# Combo_1.net
KiCad netlist of a schematic drawn in Altium Designer
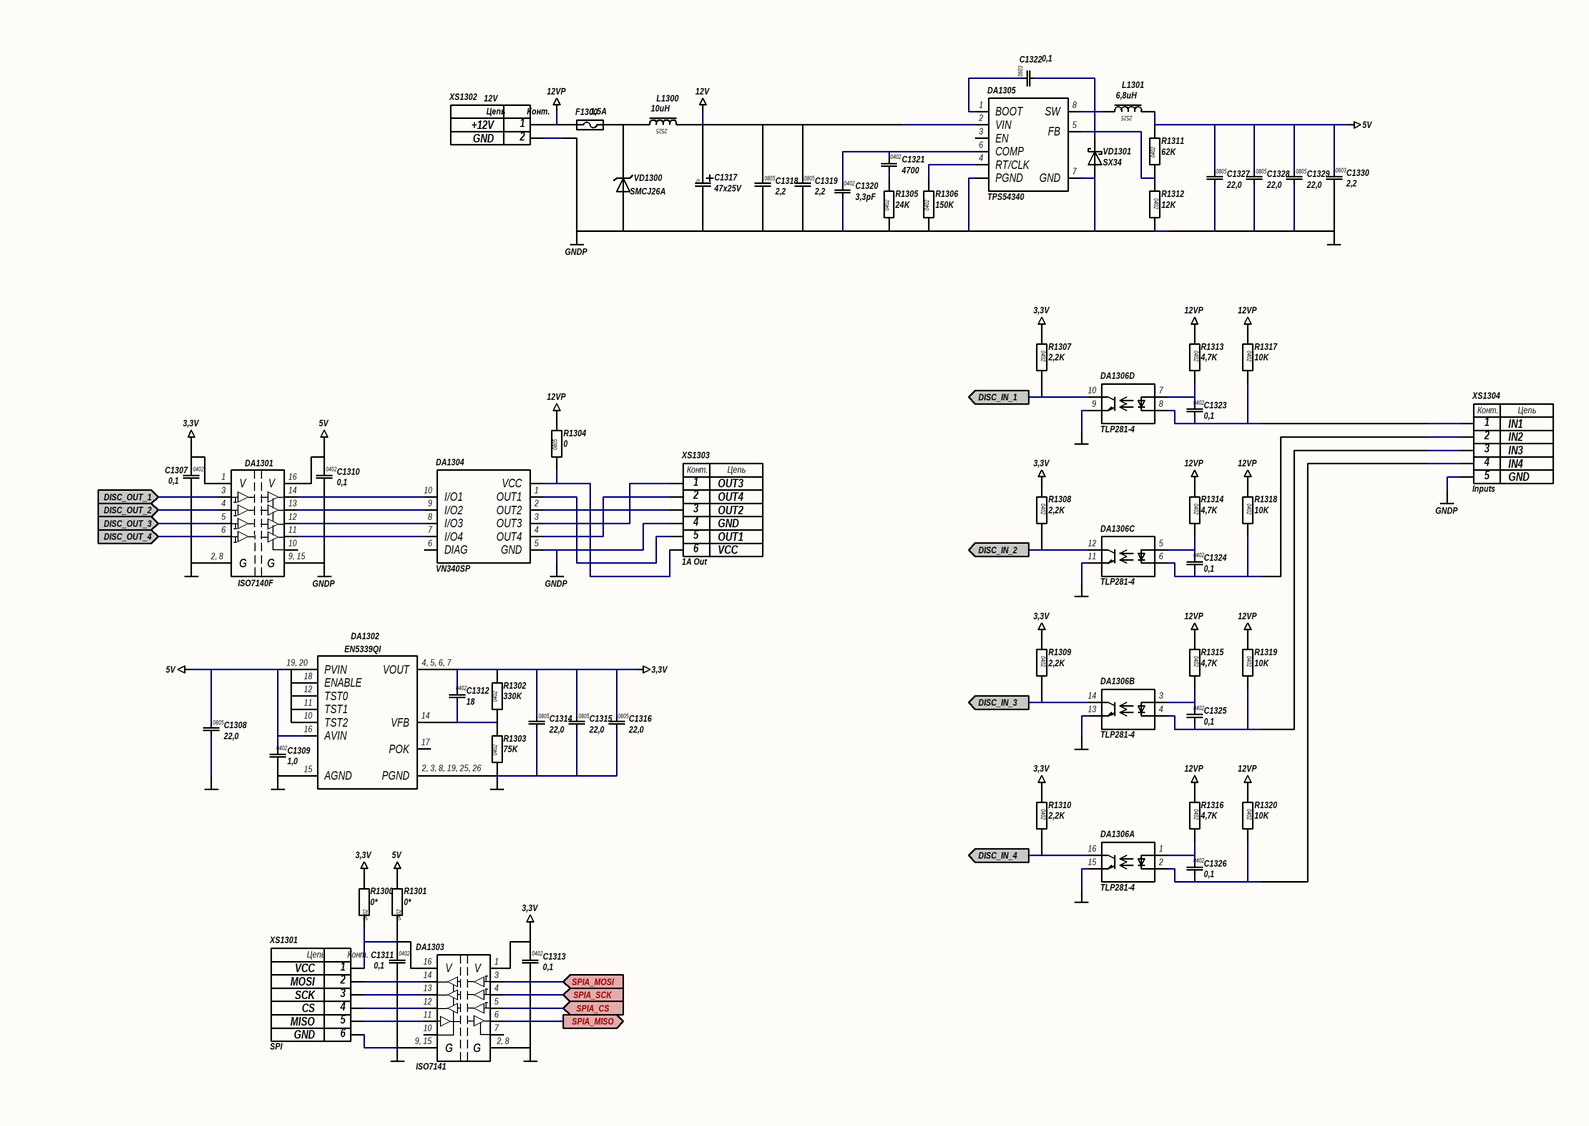
[diagram p0: Combo 1.SchDoc]

(export (version "E")
  (design (tool "Eeschema 10.0.6"))
  (components
    (comp (ref "*1300")
      (value "Перемычка")
      (footprint "Перемычка")
      (libsource (lib "EwgPassive") (part "Перемычка"))
    )
    (comp (ref "C1307")
      (value "0,1")
      (footprint "CAP0402")
      (description "Конденсатор чип")
      (libsource (lib "EwgPassive") (part "CAP_0402"))
    )
    (comp (ref "C1308")
      (value "22,0")
      (footprint "CAP0805")
      (description "Конденсатор чип")
      (libsource (lib "EwgPassive") (part "CAP_0805"))
    )
    (comp (ref "C1309")
      (value "1,0")
      (footprint "CAP0402")
      (description "Конденсатор чип")
      (libsource (lib "EwgPassive") (part "CAP_0402"))
    )
    (comp (ref "C1310")
      (value "0,1")
      (footprint "CAP0402")
      (description "Конденсатор чип")
      (libsource (lib "EwgPassive") (part "CAP_0402"))
    )
    (comp (ref "C1311")
      (value "0,1")
      (footprint "CAP0402")
      (description "Конденсатор чип")
      (libsource (lib "EwgPassive") (part "CAP_0402"))
    )
    (comp (ref "C1312")
      (value "18")
      (footprint "CAP0402")
      (description "Конденсатор чип")
      (libsource (lib "EwgPassive") (part "CAP_0402"))
    )
    (comp (ref "C1313")
      (value "0,1")
      (footprint "CAP0402")
      (description "Конденсатор чип")
      (libsource (lib "EwgPassive") (part "CAP_0402"))
    )
    (comp (ref "C1314")
      (value "22,0")
      (footprint "CAP0805")
      (description "Конденсатор чип")
      (libsource (lib "EwgPassive") (part "CAP_0805"))
    )
    (comp (ref "C1315")
      (value "22,0")
      (footprint "CAP0805")
      (description "Конденсатор чип")
      (libsource (lib "EwgPassive") (part "CAP_0805"))
    )
    (comp (ref "C1316")
      (value "22,0")
      (footprint "CAP0805")
      (description "Конденсатор чип")
      (libsource (lib "EwgPassive") (part "CAP_0805"))
    )
    (comp (ref "C1317")
      (value "47x25V")
      (footprint "CAP_D")
      (description "Конденсатор танталовый")
      (libsource (lib "EwgPassive") (part "CAP_D"))
    )
    (comp (ref "C1318")
      (value "2,2")
      (footprint "CAP0805")
      (description "Конденсатор чип")
      (libsource (lib "EwgPassive") (part "CAP_0805"))
    )
    (comp (ref "C1319")
      (value "2,2")
      (footprint "CAP0805")
      (description "Конденсатор чип")
      (libsource (lib "EwgPassive") (part "CAP_0805"))
    )
    (comp (ref "C1320")
      (value "3,3pF")
      (footprint "CAP0402")
      (description "Конденсатор чип")
      (libsource (lib "EwgPassive") (part "CAP_0402"))
    )
    (comp (ref "C1321")
      (value "4700")
      (footprint "CAP0402")
      (description "Конденсатор чип")
      (libsource (lib "EwgPassive") (part "CAP_0402"))
    )
    (comp (ref "C1322")
      (value "0,1")
      (footprint "CAP0603")
      (description "Конденсатор чип")
      (libsource (lib "EwgPassive") (part "CAP_0603"))
    )
    (comp (ref "C1323")
      (value "0,1")
      (footprint "CAP0402")
      (description "Конденсатор чип")
      (libsource (lib "EwgPassive") (part "CAP_0402"))
    )
    (comp (ref "C1324")
      (value "0,1")
      (footprint "CAP0402")
      (description "Конденсатор чип")
      (libsource (lib "EwgPassive") (part "CAP_0402"))
    )
    (comp (ref "C1325")
      (value "0,1")
      (footprint "CAP0402")
      (description "Конденсатор чип")
      (libsource (lib "EwgPassive") (part "CAP_0402"))
    )
    (comp (ref "C1326")
      (value "0,1")
      (footprint "CAP0402")
      (description "Конденсатор чип")
      (libsource (lib "EwgPassive") (part "CAP_0402"))
    )
    (comp (ref "C1327")
      (value "22,0")
      (footprint "CAP0805")
      (description "Конденсатор чип")
      (libsource (lib "EwgPassive") (part "CAP_0805"))
    )
    (comp (ref "C1328")
      (value "22,0")
      (footprint "CAP0805")
      (description "Конденсатор чип")
      (libsource (lib "EwgPassive") (part "CAP_0805"))
    )
    (comp (ref "C1329")
      (value "22,0")
      (footprint "CAP0805")
      (description "Конденсатор чип")
      (libsource (lib "EwgPassive") (part "CAP_0805"))
    )
    (comp (ref "C1330")
      (value "2,2")
      (footprint "CAP0603")
      (description "Конденсатор чип")
      (libsource (lib "EwgPassive") (part "CAP_0603"))
    )
    (comp (ref "DA1301")
      (value "ISO7140F")
      (footprint "TSSOP16")
      (description "Цифровой изолятор 4 вых")
      (libsource (lib "EwgOpto") (part "ISO7140F"))
    )
    (comp (ref "DA1302")
      (value "EN5339QI")
      (footprint "EN5339QI")
      (description "DC преобразователь понижающий")
      (libsource (lib "EwgMicrochips") (part "EN5339QI"))
    )
    (comp (ref "DA1303")
      (value "ISO7141")
      (footprint "TSSOP16")
      (description "Цифровой изолятор 3 вх 1 вых")
      (libsource (lib "EwgOpto") (part "ISO7141"))
    )
    (comp (ref "DA1304")
      (value "VN340SP")
      (footprint "PowerSO10")
      (description "Драйвер MOSFET верхнего плеча 4 шт.")
      (libsource (lib "EwgMicrochips") (part "VN340SP"))
    )
    (comp (ref "DA1305")
      (value "TPS54340")
      (footprint "SO8-3.9_P")
      (description "DC преобразователь понижающий")
      (libsource (lib "EwgMicrochips") (part "TPS54340"))
    )
    (comp (ref "DA1306")
      (value "TLP281-4")
      (footprint "SOP16")
      (description "Оптопара 4 канала")
      (libsource (lib "EwgOpto") (part "TLP281-4_1"))
    )
    (comp (ref "F1300")
      (value "1,5A")
      (footprint "MF-MSMF")
      (description "Предохранитель самовосстанавливающийся")
      (libsource (lib "EwgPassive") (part "MF-MSMF"))
    )
    (comp (ref "L1300")
      (value "10uH")
      (footprint "IND2525")
      (description "Индуктивность чип")
      (libsource (lib "EwgPassive") (part "IND_2525"))
    )
    (comp (ref "L1301")
      (value "6,8uH")
      (footprint "IND2525")
      (description "Индуктивность чип")
      (libsource (lib "EwgPassive") (part "IND_2525"))
    )
    (comp (ref "R1300")
      (value "0*")
      (footprint "RES0402")
      (description "Резистор чип")
      (libsource (lib "") (part "RES_0402_2"))
    )
    (comp (ref "R1301")
      (value "0*")
      (footprint "RES0402")
      (description "Резистор чип")
      (libsource (lib "") (part "RES_0402_2"))
    )
    (comp (ref "R1302")
      (value "330K")
      (footprint "RES0402")
      (description "Резистор чип")
      (libsource (lib "") (part "RES_0402_2"))
    )
    (comp (ref "R1303")
      (value "75K")
      (footprint "RES0402")
      (description "Резистор чип")
      (libsource (lib "") (part "RES_0402_2"))
    )
    (comp (ref "R1304")
      (value "0")
      (footprint "RES0805")
      (description "Резистор чип")
      (libsource (lib "EwgPassive") (part "RES_0805"))
    )
    (comp (ref "R1305")
      (value "24K")
      (footprint "RES0402")
      (description "Резистор чип")
      (libsource (lib "") (part "RES_0402_1"))
    )
    (comp (ref "R1306")
      (value "150K")
      (footprint "RES0402")
      (description "Резистор чип")
      (libsource (lib "") (part "RES_0402_1"))
    )
    (comp (ref "R1307")
      (value "2,2K")
      (footprint "RES0402")
      (description "Резистор чип")
      (libsource (lib "EwgPassive") (part "RES_0402"))
    )
    (comp (ref "R1308")
      (value "2,2K")
      (footprint "RES0402")
      (description "Резистор чип")
      (libsource (lib "EwgPassive") (part "RES_0402"))
    )
    (comp (ref "R1309")
      (value "2,2K")
      (footprint "RES0402")
      (description "Резистор чип")
      (libsource (lib "EwgPassive") (part "RES_0402"))
    )
    (comp (ref "R1310")
      (value "2,2K")
      (footprint "RES0402")
      (description "Резистор чип")
      (libsource (lib "EwgPassive") (part "RES_0402"))
    )
    (comp (ref "R1311")
      (value "62K")
      (footprint "RES0402")
      (description "Резистор чип")
      (libsource (lib "") (part "RES_0402_1"))
    )
    (comp (ref "R1312")
      (value "12K")
      (footprint "RES0402")
      (description "Резистор чип")
      (libsource (lib "EwgPassive") (part "RES_0402"))
    )
    (comp (ref "R1313")
      (value "4,7K")
      (footprint "RES0402")
      (description "Резистор чип")
      (libsource (lib "EwgPassive") (part "RES_0402"))
    )
    (comp (ref "R1314")
      (value "4,7K")
      (footprint "RES0402")
      (description "Резистор чип")
      (libsource (lib "EwgPassive") (part "RES_0402"))
    )
    (comp (ref "R1315")
      (value "4,7K")
      (footprint "RES0402")
      (description "Резистор чип")
      (libsource (lib "EwgPassive") (part "RES_0402"))
    )
    (comp (ref "R1316")
      (value "4,7K")
      (footprint "RES0402")
      (description "Резистор чип")
      (libsource (lib "EwgPassive") (part "RES_0402"))
    )
    (comp (ref "R1317")
      (value "10K")
      (footprint "RES0402")
      (description "Резистор чип")
      (libsource (lib "EwgPassive") (part "RES_0402"))
    )
    (comp (ref "R1318")
      (value "10K")
      (footprint "RES0402")
      (description "Резистор чип")
      (libsource (lib "EwgPassive") (part "RES_0402"))
    )
    (comp (ref "R1319")
      (value "10K")
      (footprint "RES0402")
      (description "Резистор чип")
      (libsource (lib "EwgPassive") (part "RES_0402"))
    )
    (comp (ref "R1320")
      (value "10K")
      (footprint "RES0402")
      (description "Резистор чип")
      (libsource (lib "EwgPassive") (part "RES_0402"))
    )
    (comp (ref "VD1300")
      (value "SMCJ26A")
      (footprint "SMC")
      (description "Диод TVS")
      (libsource (lib "EwgActive") (part "SMCJxx"))
    )
    (comp (ref "VD1301")
      (value "SX34")
      (footprint "SMA")
      (description "Диод Шоттки")
      (fields (field (name "НАИМЕНОВАНИЕ") "SX34"))
      (libsource (lib "EwgActive") (part "SX34"))
    )
    (comp (ref "XS1301")
      (value "SPI")
      (footprint "MW-6M")
      (description "Разъем")
      (libsource (lib "EwgConnectors") (part "Разъем6"))
    )
    (comp (ref "XS1302")
      (value "12V")
      (footprint "uF-2X1R")
      (description "Разъем")
      (libsource (lib "EwgConnectors") (part "Разъем2_1"))
    )
    (comp (ref "XS1303")
      (value "1A Out")
      (footprint "uF-2X3R")
      (description "Разъем")
      (libsource (lib "") (part "Разъем6_1"))
    )
    (comp (ref "XS1304")
      (value "Inputs")
      (footprint "MW-5M")
      (description "Разъем")
      (libsource (lib "EwgConnectors") (part "Разъем5"))
    )
  )
  (nets
    (net (code "1") (name "/DISC_IN_1") (class "Default")
      (node (ref "DA1306") (pin "10") (pintype "passive"))
      (node (ref "R1307") (pin "2") (pintype "passive"))
    )
    (net (code "2") (name "/DISC_IN_2") (class "Default")
      (node (ref "DA1306") (pin "12") (pintype "passive"))
      (node (ref "R1308") (pin "2") (pintype "passive"))
    )
    (net (code "3") (name "/DISC_IN_3") (class "Default")
      (node (ref "DA1306") (pin "14") (pintype "passive"))
      (node (ref "R1309") (pin "2") (pintype "passive"))
    )
    (net (code "4") (name "/DISC_IN_4") (class "Default")
      (node (ref "DA1306") (pin "16") (pintype "passive"))
      (node (ref "R1310") (pin "2") (pintype "passive"))
    )
    (net (code "5") (name "/DISC_OUT_1") (class "Default")
      (node (ref "DA1301") (pin "3") (pinfunction "INA_3") (pintype "passive"))
    )
    (net (code "6") (name "/DISC_OUT_2") (class "Default")
      (node (ref "DA1301") (pin "4") (pinfunction "INB_4") (pintype "passive"))
    )
    (net (code "7") (name "/DISC_OUT_3") (class "Default")
      (node (ref "DA1301") (pin "5") (pinfunction "INC_5") (pintype "passive"))
    )
    (net (code "8") (name "/DISC_OUT_4") (class "Default")
      (node (ref "DA1301") (pin "6") (pinfunction "IND_6") (pintype "passive"))
    )
    (net (code "9") (name "/SPIA_CS") (class "Default")
      (node (ref "DA1303") (pin "5") (pinfunction "INC_5") (pintype "passive"))
    )
    (net (code "10") (name "/SPIA_MISO") (class "Default")
      (node (ref "DA1303") (pin "6") (pinfunction "OUTD_6") (pintype "passive"))
    )
    (net (code "11") (name "/SPIA_MOSI") (class "Default")
      (node (ref "DA1303") (pin "3") (pinfunction "INA_3") (pintype "passive"))
    )
    (net (code "12") (name "/SPIA_SCK") (class "Default")
      (node (ref "DA1303") (pin "4") (pinfunction "INB_4") (pintype "passive"))
    )
    (net (code "13") (name "3,3V") (class "Default")
      (node (ref "C1307") (pin "1") (pintype "passive"))
      (node (ref "C1312") (pin "1") (pintype "passive"))
      (node (ref "C1313") (pin "1") (pintype "passive"))
      (node (ref "C1314") (pin "1") (pintype "passive"))
      (node (ref "C1315") (pin "1") (pintype "passive"))
      (node (ref "C1316") (pin "1") (pintype "passive"))
      (node (ref "DA1301") (pin "1") (pinfunction "V_1") (pintype "power_in"))
      (node (ref "DA1302") (pin "4") (pinfunction "VOUT_4") (pintype "passive"))
      (node (ref "DA1302") (pin "5") (pinfunction "VOUT_5") (pintype "passive"))
      (node (ref "DA1302") (pin "6") (pinfunction "VOUT_6") (pintype "passive"))
      (node (ref "DA1302") (pin "7") (pinfunction "VOUT_7") (pintype "passive"))
      (node (ref "DA1303") (pin "1") (pinfunction "V_1") (pintype "power_in"))
      (node (ref "R1300") (pin "2") (pintype "passive"))
      (node (ref "R1302") (pin "2") (pintype "passive"))
      (node (ref "R1307") (pin "1") (pintype "passive"))
      (node (ref "R1308") (pin "1") (pintype "passive"))
      (node (ref "R1309") (pin "1") (pintype "passive"))
      (node (ref "R1310") (pin "1") (pintype "passive"))
    )
    (net (code "14") (name "5V") (class "Default")
      (node (ref "C1308") (pin "1") (pintype "passive"))
      (node (ref "C1309") (pin "1") (pintype "passive"))
      (node (ref "C1310") (pin "1") (pintype "passive"))
      (node (ref "C1327") (pin "1") (pintype "passive"))
      (node (ref "C1328") (pin "1") (pintype "passive"))
      (node (ref "C1329") (pin "1") (pintype "passive"))
      (node (ref "C1330") (pin "1") (pintype "passive"))
      (node (ref "DA1301") (pin "16") (pinfunction "V_16") (pintype "power_in"))
      (node (ref "DA1302") (pin "10") (pinfunction "TST2_10") (pintype "passive"))
      (node (ref "DA1302") (pin "11") (pinfunction "TST1_11") (pintype "passive"))
      (node (ref "DA1302") (pin "12") (pinfunction "TST0_12") (pintype "passive"))
      (node (ref "DA1302") (pin "16") (pinfunction "AVIN_16") (pintype "passive"))
      (node (ref "DA1302") (pin "18") (pinfunction "ENABLE_18") (pintype "passive"))
      (node (ref "DA1302") (pin "19") (pinfunction "PVIN_19") (pintype "passive"))
      (node (ref "DA1302") (pin "20") (pinfunction "PVIN_20") (pintype "passive"))
      (node (ref "L1301") (pin "2") (pintype "passive"))
      (node (ref "R1301") (pin "2") (pintype "passive"))
      (node (ref "R1311") (pin "2") (pintype "passive"))
    )
    (net (code "15") (name "12V") (class "Default")
      (node (ref "C1317") (pin "1") (pintype "passive"))
      (node (ref "C1318") (pin "1") (pintype "passive"))
      (node (ref "C1319") (pin "1") (pintype "passive"))
      (node (ref "DA1305") (pin "2") (pinfunction "VIN_2") (pintype "passive"))
      (node (ref "L1300") (pin "2") (pintype "passive"))
    )
    (net (code "16") (name "12VP") (class "Default")
      (node (ref "F1300") (pin "1") (pintype "passive"))
      (node (ref "R1304") (pin "2") (pintype "passive"))
      (node (ref "R1313") (pin "1") (pintype "passive"))
      (node (ref "R1314") (pin "1") (pintype "passive"))
      (node (ref "R1315") (pin "1") (pintype "passive"))
      (node (ref "R1316") (pin "1") (pintype "passive"))
      (node (ref "R1317") (pin "1") (pintype "passive"))
      (node (ref "R1318") (pin "1") (pintype "passive"))
      (node (ref "R1319") (pin "1") (pintype "passive"))
      (node (ref "R1320") (pin "1") (pintype "passive"))
      (node (ref "XS1302") (pin "1") (pinfunction "+12V_1") (pintype "passive"))
    )
    (net (code "17") (name "GND") (class "Default")
      (node (ref "*1300") (pin "2") (pintype "passive"))
      (node (ref "C1307") (pin "2") (pintype "passive"))
      (node (ref "C1308") (pin "2") (pintype "passive"))
      (node (ref "C1309") (pin "2") (pintype "passive"))
      (node (ref "C1311") (pin "2") (pintype "passive"))
      (node (ref "C1313") (pin "2") (pintype "passive"))
      (node (ref "C1314") (pin "2") (pintype "passive"))
      (node (ref "C1315") (pin "2") (pintype "passive"))
      (node (ref "C1316") (pin "2") (pintype "passive"))
      (node (ref "C1327") (pin "2") (pintype "passive"))
      (node (ref "C1328") (pin "2") (pintype "passive"))
      (node (ref "C1329") (pin "2") (pintype "passive"))
      (node (ref "C1330") (pin "2") (pintype "passive"))
      (node (ref "DA1301") (pin "2") (pinfunction "G_2") (pintype "power_in"))
      (node (ref "DA1301") (pin "8") (pinfunction "G_8") (pintype "passive"))
      (node (ref "DA1302") (pin "15") (pinfunction "AGND_15") (pintype "passive"))
      (node (ref "DA1302") (pin "2") (pinfunction "PGND_2") (pintype "passive"))
      (node (ref "DA1302") (pin "25") (pinfunction "PGND_25") (pintype "passive"))
      (node (ref "DA1302") (pin "26") (pinfunction "PGND_26") (pintype "passive"))
      (node (ref "DA1302") (pin "3") (pinfunction "PGND_3") (pintype "passive"))
      (node (ref "DA1302") (pin "8") (pinfunction "PGND_8") (pintype "passive"))
      (node (ref "DA1302") (pin "9") (pinfunction "PGND_9") (pintype "passive"))
      (node (ref "DA1303") (pin "15") (pinfunction "G_15") (pintype "power_in"))
      (node (ref "DA1303") (pin "2") (pinfunction "G_2") (pintype "power_in"))
      (node (ref "DA1303") (pin "8") (pinfunction "G_8") (pintype "passive"))
      (node (ref "DA1303") (pin "9") (pinfunction "G_9") (pintype "passive"))
      (node (ref "DA1306") (pin "11") (pintype "passive"))
      (node (ref "DA1306") (pin "13") (pintype "passive"))
      (node (ref "DA1306") (pin "15") (pintype "passive"))
      (node (ref "DA1306") (pin "9") (pintype "passive"))
      (node (ref "R1303") (pin "1") (pintype "passive"))
      (node (ref "XS1301") (pin "6") (pinfunction "GND_6") (pintype "passive"))
    )
    (net (code "18") (name "GNDP") (class "Default")
      (node (ref "*1300") (pin "1") (pintype "passive"))
      (node (ref "C1310") (pin "2") (pintype "passive"))
      (node (ref "C1317") (pin "2") (pintype "passive"))
      (node (ref "C1318") (pin "2") (pintype "passive"))
      (node (ref "C1319") (pin "2") (pintype "passive"))
      (node (ref "C1320") (pin "2") (pintype "passive"))
      (node (ref "DA1301") (pin "15") (pinfunction "G_15") (pintype "power_in"))
      (node (ref "DA1301") (pin "9") (pinfunction "G_9") (pintype "passive"))
      (node (ref "DA1304") (pin "5") (pinfunction "GND_5") (pintype "passive"))
      (node (ref "DA1305") (pin "0") (pinfunction "PGND_0") (pintype "passive"))
      (node (ref "DA1305") (pin "7") (pinfunction "GND_7") (pintype "passive"))
      (node (ref "R1305") (pin "1") (pintype "passive"))
      (node (ref "R1306") (pin "1") (pintype "passive"))
      (node (ref "R1312") (pin "2") (pintype "passive"))
      (node (ref "VD1300") (pin "1") (pintype "passive"))
      (node (ref "VD1301") (pin "1") (pintype "passive"))
      (node (ref "XS1302") (pin "2") (pinfunction "GND_2") (pintype "passive"))
      (node (ref "XS1303") (pin "4") (pinfunction "GND_4") (pintype "passive"))
      (node (ref "XS1304") (pin "5") (pinfunction "GND_5") (pintype "passive"))
    )
    (net (code "19") (name "Net-(C1321-Pad2)") (class "Default")
      (node (ref "C1321") (pin "2") (pintype "passive"))
      (node (ref "R1305") (pin "2") (pintype "passive"))
    )
    (net (code "20") (name "Net-(C1323-Pad1)") (class "Default")
      (node (ref "C1323") (pin "1") (pintype "passive"))
      (node (ref "DA1306") (pin "7") (pintype "passive"))
      (node (ref "R1313") (pin "2") (pintype "passive"))
    )
    (net (code "21") (name "Net-(C1324-Pad1)") (class "Default")
      (node (ref "C1324") (pin "1") (pintype "passive"))
      (node (ref "DA1306") (pin "5") (pintype "passive"))
      (node (ref "R1314") (pin "2") (pintype "passive"))
    )
    (net (code "22") (name "Net-(C1325-Pad1)") (class "Default")
      (node (ref "C1325") (pin "1") (pintype "passive"))
      (node (ref "DA1306") (pin "3") (pintype "passive"))
      (node (ref "R1315") (pin "2") (pintype "passive"))
    )
    (net (code "23") (name "Net-(C1326-Pad1)") (class "Default")
      (node (ref "C1326") (pin "1") (pintype "passive"))
      (node (ref "DA1306") (pin "1") (pintype "passive"))
      (node (ref "R1316") (pin "2") (pintype "passive"))
    )
    (net (code "24") (name "Net-(DA1301-OUTA)") (class "Default")
      (node (ref "DA1301") (pin "14") (pinfunction "OUTA_14") (pintype "passive"))
      (node (ref "DA1304") (pin "10") (pinfunction "I/O1_10") (pintype "passive"))
    )
    (net (code "25") (name "Net-(DA1301-OUTB)") (class "Default")
      (node (ref "DA1301") (pin "13") (pinfunction "OUTB_13") (pintype "passive"))
      (node (ref "DA1304") (pin "9") (pinfunction "I/O2_9") (pintype "passive"))
    )
    (net (code "26") (name "Net-(DA1301-OUTC)") (class "Default")
      (node (ref "DA1301") (pin "12") (pinfunction "OUTC_12") (pintype "passive"))
      (node (ref "DA1304") (pin "8") (pinfunction "I/O3_8") (pintype "passive"))
    )
    (net (code "27") (name "Net-(DA1301-OUTD)") (class "Default")
      (node (ref "DA1301") (pin "11") (pinfunction "OUTD_11") (pintype "passive"))
      (node (ref "DA1304") (pin "7") (pinfunction "I/O4_7") (pintype "passive"))
    )
    (net (code "28") (name "Net-(DA1302-VFB)") (class "Default")
      (node (ref "C1312") (pin "2") (pintype "passive"))
      (node (ref "DA1302") (pin "14") (pinfunction "VFB_14") (pintype "passive"))
      (node (ref "R1302") (pin "1") (pintype "passive"))
      (node (ref "R1303") (pin "2") (pintype "passive"))
    )
    (net (code "29") (name "Net-(DA1303-IND)") (class "Default")
      (node (ref "DA1303") (pin "11") (pinfunction "IND_11") (pintype "passive"))
      (node (ref "XS1301") (pin "5") (pinfunction "MISO_5") (pintype "passive"))
    )
    (net (code "30") (name "Net-(DA1303-OUTA)") (class "Default")
      (node (ref "DA1303") (pin "14") (pinfunction "OUTA_14") (pintype "passive"))
      (node (ref "XS1301") (pin "2") (pinfunction "MOSI_2") (pintype "passive"))
    )
    (net (code "31") (name "Net-(DA1303-OUTB)") (class "Default")
      (node (ref "DA1303") (pin "13") (pinfunction "OUTB_13") (pintype "passive"))
      (node (ref "XS1301") (pin "3") (pinfunction "SCK_3") (pintype "passive"))
    )
    (net (code "32") (name "Net-(DA1303-OUTC)") (class "Default")
      (node (ref "DA1303") (pin "12") (pinfunction "OUTC_12") (pintype "passive"))
      (node (ref "XS1301") (pin "4") (pinfunction "CS_4") (pintype "passive"))
    )
    (net (code "33") (name "Net-(DA1304-OUT1)") (class "Default")
      (node (ref "DA1304") (pin "1") (pinfunction "OUT1_1") (pintype "passive"))
      (node (ref "XS1303") (pin "5") (pinfunction "OUT1_5") (pintype "passive"))
    )
    (net (code "34") (name "Net-(DA1304-OUT2)") (class "Default")
      (node (ref "DA1304") (pin "2") (pinfunction "OUT2_2") (pintype "passive"))
      (node (ref "XS1303") (pin "3") (pinfunction "OUT2_3") (pintype "passive"))
    )
    (net (code "35") (name "Net-(DA1304-OUT3)") (class "Default")
      (node (ref "DA1304") (pin "3") (pinfunction "OUT3_3") (pintype "passive"))
      (node (ref "XS1303") (pin "1") (pinfunction "OUT3_1") (pintype "passive"))
    )
    (net (code "36") (name "Net-(DA1304-OUT4)") (class "Default")
      (node (ref "DA1304") (pin "4") (pinfunction "OUT4_4") (pintype "passive"))
      (node (ref "XS1303") (pin "2") (pinfunction "OUT4_2") (pintype "passive"))
    )
    (net (code "37") (name "Net-(DA1304-VCC)") (class "Default")
      (node (ref "DA1304") (pin "0") (pinfunction "VCC_0") (pintype "passive"))
      (node (ref "R1304") (pin "1") (pintype "passive"))
      (node (ref "XS1303") (pin "6") (pinfunction "VCC_6") (pintype "passive"))
    )
    (net (code "38") (name "Net-(DA1305-BOOT)") (class "Default")
      (node (ref "C1322") (pin "1") (pintype "passive"))
      (node (ref "DA1305") (pin "1") (pinfunction "BOOT_1") (pintype "passive"))
    )
    (net (code "39") (name "Net-(DA1305-COMP)") (class "Default")
      (node (ref "C1320") (pin "1") (pintype "passive"))
      (node (ref "C1321") (pin "1") (pintype "passive"))
      (node (ref "DA1305") (pin "6") (pinfunction "COMP_6") (pintype "passive"))
    )
    (net (code "40") (name "Net-(DA1305-FB)") (class "Default")
      (node (ref "DA1305") (pin "5") (pinfunction "FB_5") (pintype "passive"))
      (node (ref "R1311") (pin "1") (pintype "passive"))
      (node (ref "R1312") (pin "1") (pintype "passive"))
    )
    (net (code "41") (name "Net-(DA1305-RT{slash}CLK)") (class "Default")
      (node (ref "DA1305") (pin "4") (pinfunction "RT/CLK_4") (pintype "passive"))
      (node (ref "R1306") (pin "2") (pintype "passive"))
    )
    (net (code "42") (name "Net-(DA1305-SW)") (class "Default")
      (node (ref "C1322") (pin "2") (pintype "passive"))
      (node (ref "DA1305") (pin "8") (pinfunction "SW_8") (pintype "passive"))
      (node (ref "L1301") (pin "1") (pintype "passive"))
      (node (ref "VD1301") (pin "2") (pintype "passive"))
    )
    (net (code "43") (name "Net-(F1300-Pad2)") (class "Default")
      (node (ref "F1300") (pin "2") (pintype "passive"))
      (node (ref "L1300") (pin "1") (pintype "passive"))
      (node (ref "VD1300") (pin "2") (pintype "passive"))
    )
    (net (code "44") (name "Net-(XS1301-VCC)") (class "Default")
      (node (ref "C1311") (pin "1") (pintype "passive"))
      (node (ref "DA1303") (pin "16") (pinfunction "V_16") (pintype "power_in"))
      (node (ref "R1300") (pin "1") (pintype "passive"))
      (node (ref "R1301") (pin "1") (pintype "passive"))
      (node (ref "XS1301") (pin "1") (pinfunction "VCC_1") (pintype "passive"))
    )
    (net (code "45") (name "Net-(XS1304-IN1)") (class "Default")
      (node (ref "C1323") (pin "2") (pintype "passive"))
      (node (ref "DA1306") (pin "8") (pintype "passive"))
      (node (ref "R1317") (pin "2") (pintype "passive"))
      (node (ref "XS1304") (pin "1") (pinfunction "IN1_1") (pintype "passive"))
    )
    (net (code "46") (name "Net-(XS1304-IN2)") (class "Default")
      (node (ref "C1324") (pin "2") (pintype "passive"))
      (node (ref "DA1306") (pin "6") (pintype "passive"))
      (node (ref "R1318") (pin "2") (pintype "passive"))
      (node (ref "XS1304") (pin "2") (pinfunction "IN2_2") (pintype "passive"))
    )
    (net (code "47") (name "Net-(XS1304-IN3)") (class "Default")
      (node (ref "C1325") (pin "2") (pintype "passive"))
      (node (ref "DA1306") (pin "4") (pintype "passive"))
      (node (ref "R1319") (pin "2") (pintype "passive"))
      (node (ref "XS1304") (pin "3") (pinfunction "IN3_3") (pintype "passive"))
    )
    (net (code "48") (name "Net-(XS1304-IN4)") (class "Default")
      (node (ref "C1326") (pin "2") (pintype "passive"))
      (node (ref "DA1306") (pin "2") (pintype "passive"))
      (node (ref "R1320") (pin "2") (pintype "passive"))
      (node (ref "XS1304") (pin "4") (pinfunction "IN4_4") (pintype "passive"))
    )
    (net (code "49") (name "unconnected-(DA1301-EN-Pad10)") (class "Default")
      (node (ref "DA1301") (pin "10") (pinfunction "EN_10") (pintype "passive"))
    )
    (net (code "50") (name "unconnected-(DA1302-POK-Pad17)") (class "Default")
      (node (ref "DA1302") (pin "17") (pinfunction "POK_17") (pintype "passive"))
    )
    (net (code "51") (name "unconnected-(DA1303-EN1-Pad7)") (class "Default")
      (node (ref "DA1303") (pin "7") (pinfunction "EN1_7") (pintype "passive"))
    )
    (net (code "52") (name "unconnected-(DA1303-EN2-Pad10)") (class "Default")
      (node (ref "DA1303") (pin "10") (pinfunction "EN2_10") (pintype "passive"))
    )
    (net (code "53") (name "unconnected-(DA1304-DIAG-Pad6)") (class "Default")
      (node (ref "DA1304") (pin "6") (pinfunction "DIAG_6") (pintype "passive"))
    )
    (net (code "54") (name "unconnected-(DA1305-EN-Pad3)") (class "Default")
      (node (ref "DA1305") (pin "3") (pinfunction "EN_3") (pintype "passive"))
    )
  )
)
